# altium_sample_nouid.net
KiCad netlist of a schematic drawn in Altium Designer
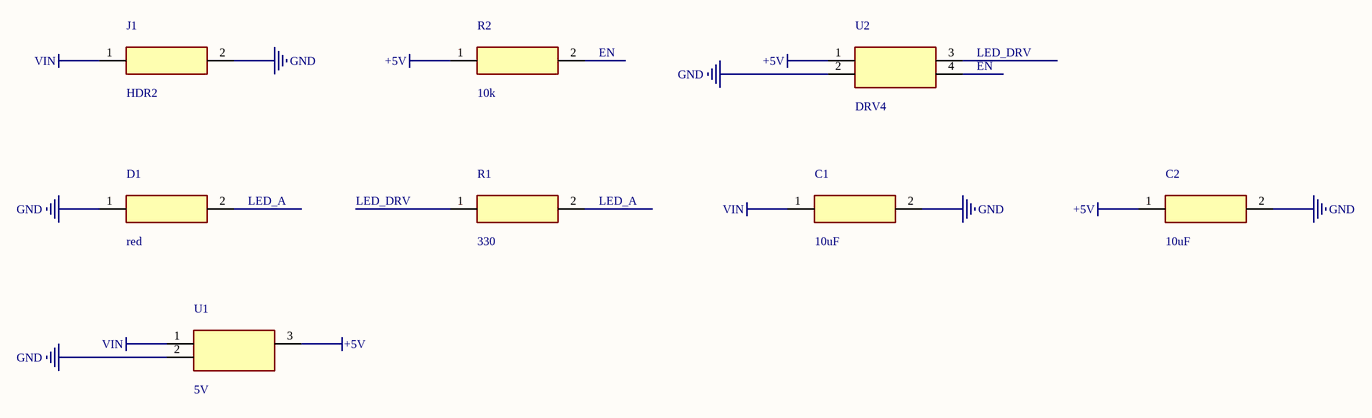
[diagram p0: altium_sample_nouid.SchDoc]

(export (version "E")
  (design (tool "Eeschema 10.0.6"))
  (components
    (comp (ref "C1")
      (value "10uF")
      (footprint "FenoliteSample:C0603")
      (libsource (lib "FenoliteSample") (part "CAP"))
    )
    (comp (ref "C2")
      (value "10uF")
      (footprint "FenoliteSample:C0603")
      (libsource (lib "FenoliteSample") (part "CAP"))
    )
    (comp (ref "D1")
      (value "red")
      (footprint "FenoliteSample:LED0603")
      (libsource (lib "FenoliteSample") (part "LED"))
    )
    (comp (ref "J1")
      (value "HDR2")
      (footprint "FenoliteSample:HDR1X2")
      (libsource (lib "FenoliteSample") (part "HDR2"))
    )
    (comp (ref "R1")
      (value "330")
      (footprint "FenoliteSample:R0603")
      (libsource (lib "FenoliteSample") (part "RES"))
    )
    (comp (ref "R2")
      (value "10k")
      (footprint "FenoliteSample:R0603")
      (libsource (lib "FenoliteSample") (part "RES"))
    )
    (comp (ref "U1")
      (value "5V")
      (footprint "FenoliteSample:SOT23")
      (libsource (lib "FenoliteSample") (part "LDO3"))
    )
    (comp (ref "U2")
      (value "DRV4")
      (footprint "FenoliteSample:SOT143")
      (libsource (lib "FenoliteSample") (part "DRV4"))
    )
  )
  (nets
    (net (code "1") (name "+5V") (class "Default")
      (node (ref "C2") (pin "1") (pinfunction "1_1") (pintype "passive"))
      (node (ref "R2") (pin "1") (pinfunction "1_1") (pintype "passive"))
      (node (ref "U1") (pin "3") (pinfunction "3_3") (pintype "passive"))
      (node (ref "U2") (pin "1") (pinfunction "1_1") (pintype "passive"))
    )
    (net (code "2") (name "/EN") (class "Default")
      (node (ref "R2") (pin "2") (pinfunction "2_2") (pintype "passive"))
      (node (ref "U2") (pin "4") (pinfunction "4_4") (pintype "passive"))
    )
    (net (code "3") (name "/LED_A") (class "Default")
      (node (ref "D1") (pin "2") (pinfunction "2_2") (pintype "passive"))
      (node (ref "R1") (pin "2") (pinfunction "2_2") (pintype "passive"))
    )
    (net (code "4") (name "/LED_DRV") (class "Default")
      (node (ref "R1") (pin "1") (pinfunction "1_1") (pintype "passive"))
      (node (ref "U2") (pin "3") (pinfunction "3_3") (pintype "passive"))
    )
    (net (code "5") (name "GND") (class "Default")
      (node (ref "C1") (pin "2") (pinfunction "2_2") (pintype "passive"))
      (node (ref "C2") (pin "2") (pinfunction "2_2") (pintype "passive"))
      (node (ref "D1") (pin "1") (pinfunction "1_1") (pintype "passive"))
      (node (ref "J1") (pin "2") (pinfunction "2_2") (pintype "passive"))
      (node (ref "U1") (pin "2") (pinfunction "2_2") (pintype "passive"))
      (node (ref "U2") (pin "2") (pinfunction "2_2") (pintype "passive"))
    )
    (net (code "6") (name "VIN") (class "Default")
      (node (ref "C1") (pin "1") (pinfunction "1_1") (pintype "passive"))
      (node (ref "J1") (pin "1") (pinfunction "1_1") (pintype "passive"))
      (node (ref "U1") (pin "1") (pinfunction "1_1") (pintype "passive"))
    )
  )
)
